# blink1_trinket0.net
KiCad netlist of a schematic drawn in EAGLE
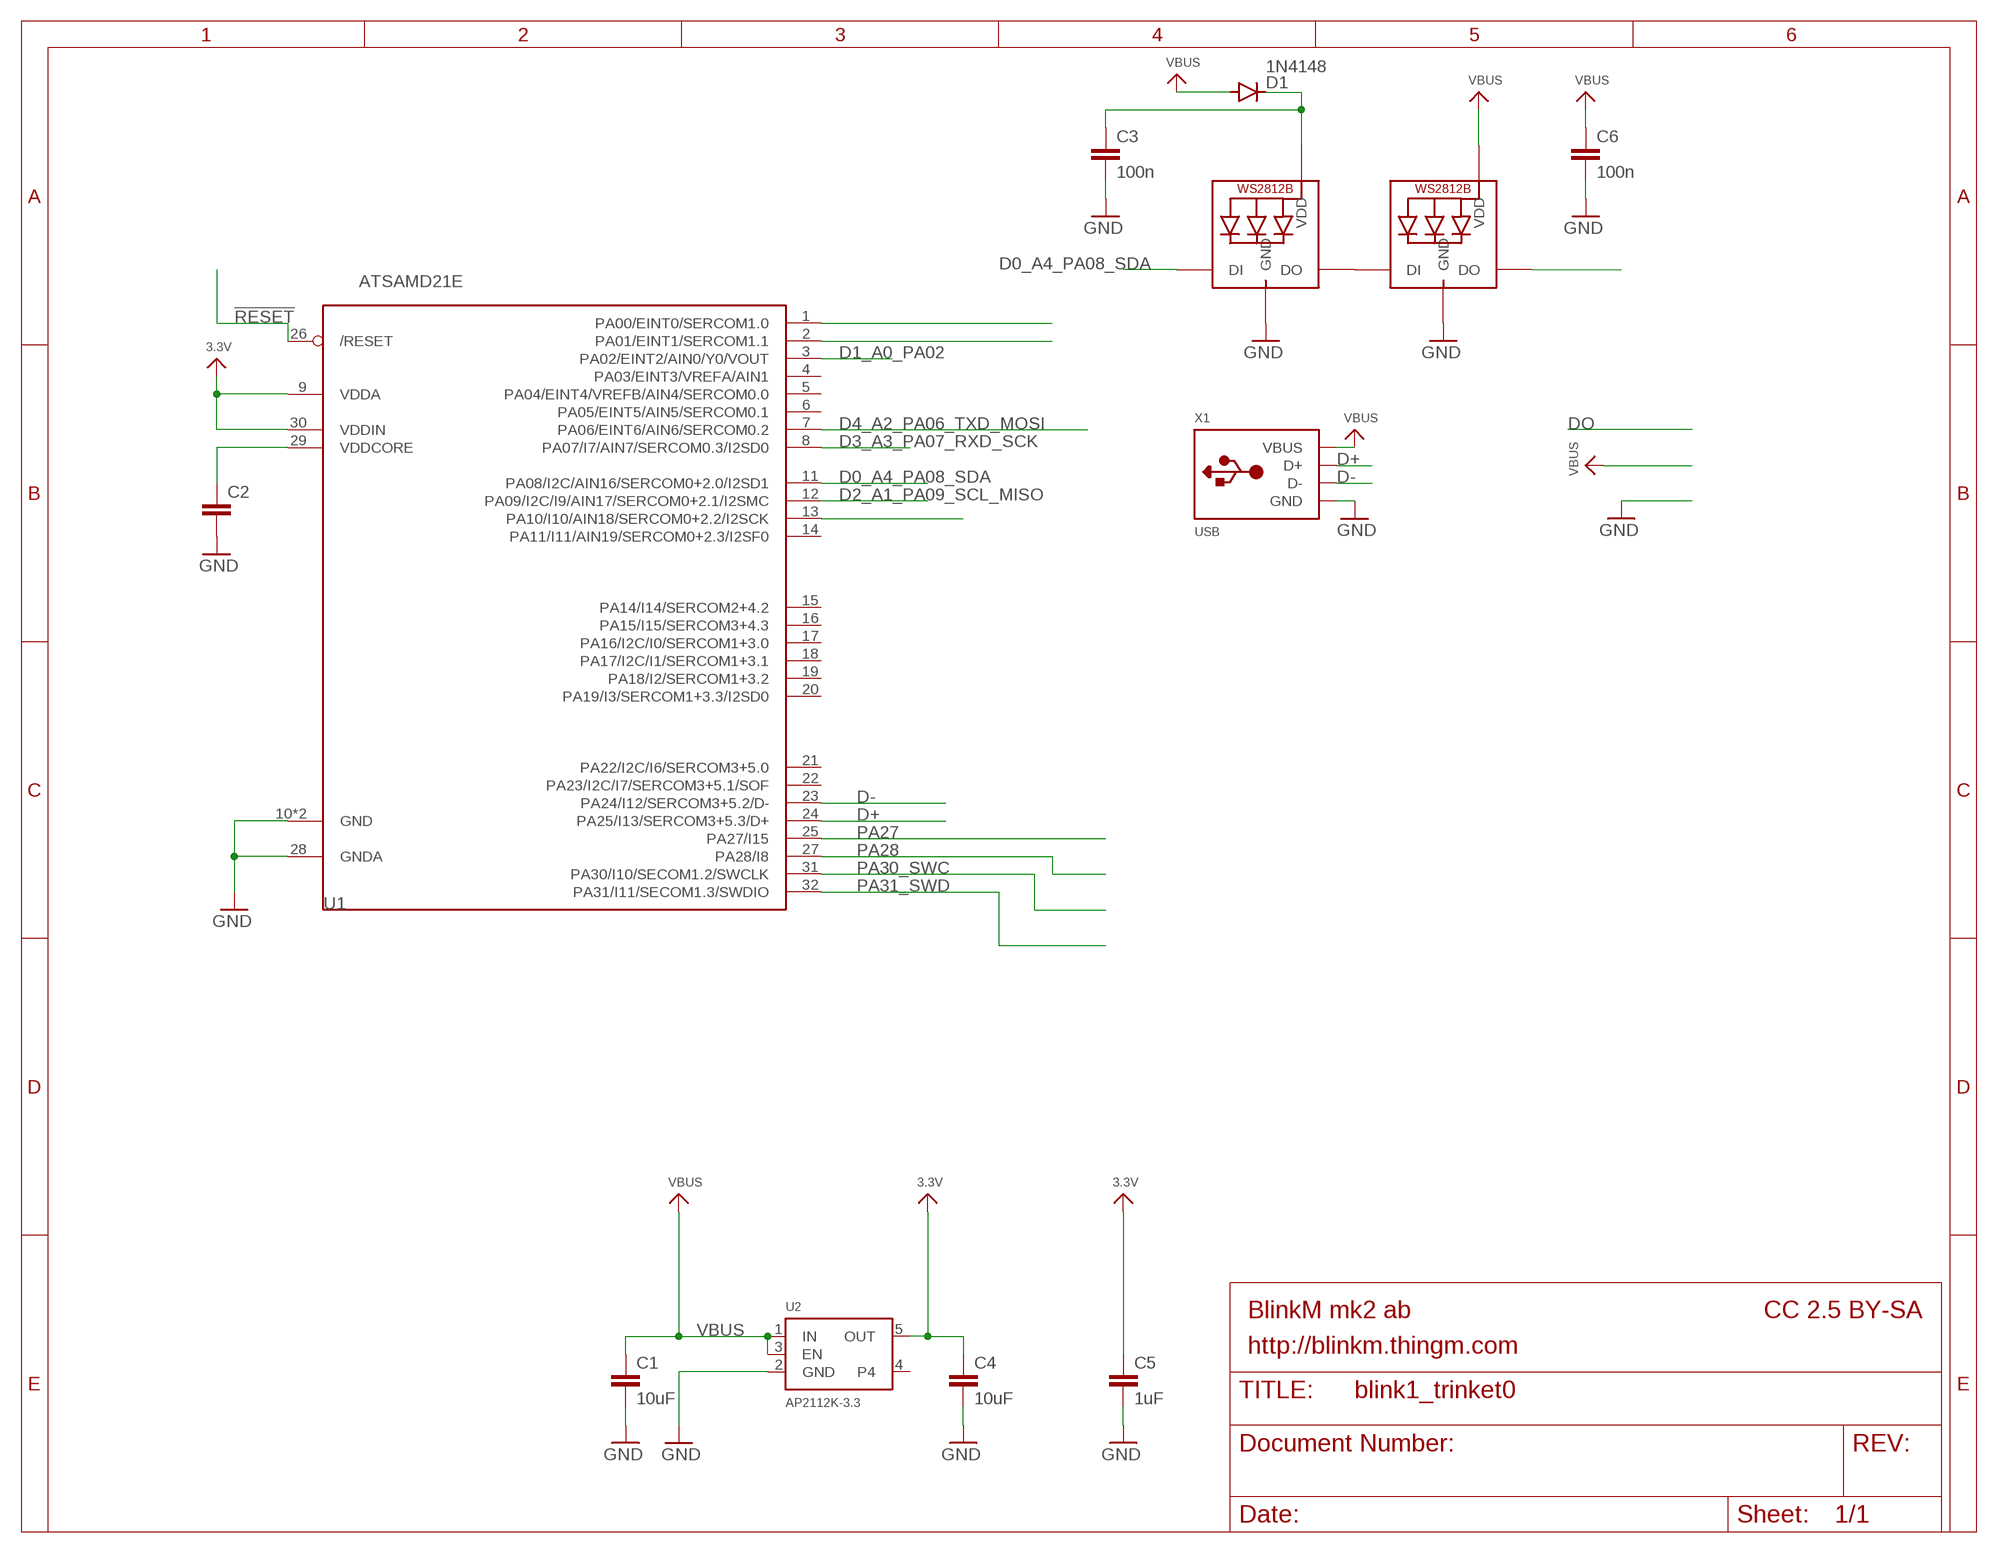
[diagram p0: schematic, sheet 1]

(export (version "E")
  (design (tool "Eeschema 10.0.6"))
  (components
    (comp (ref "C1")
      (value "10uF")
      (footprint "eagle-import:C0402")
      (libsource (lib "eagle-import") (part "C-EUC0402"))
    )
    (comp (ref "C2")
      (value "C-EUC0402")
      (footprint "eagle-import:C0402")
      (libsource (lib "eagle-import") (part "C-EUC0402"))
    )
    (comp (ref "C3")
      (value "100n")
      (footprint "eagle-import:C0402")
      (libsource (lib "eagle-import") (part "C-EUC0402"))
    )
    (comp (ref "C4")
      (value "10uF")
      (footprint "eagle-import:C0402")
      (libsource (lib "eagle-import") (part "C-EUC0402"))
    )
    (comp (ref "C5")
      (value "1uF")
      (footprint "eagle-import:C0402")
      (libsource (lib "eagle-import") (part "C-EUC0402"))
    )
    (comp (ref "C6")
      (value "100n")
      (footprint "eagle-import:C0402")
      (libsource (lib "eagle-import") (part "C-EUC0402"))
    )
    (comp (ref "D1")
      (value "1N4148")
      (footprint "eagle-import:SOD523")
      (libsource (lib "eagle-import") (part "DIODE-SOD523"))
    )
    (comp (ref "L1")
      (value "WS2812B3535")
      (footprint "eagle-import:LED3535")
      (libsource (lib "eagle-import") (part "WS2812B3535"))
    )
    (comp (ref "L2")
      (value "WS2812B3535")
      (footprint "eagle-import:LED3535")
      (libsource (lib "eagle-import") (part "WS2812B3535"))
    )
    (comp (ref "U1")
      (value "ATSAMD21E")
      (footprint "eagle-import:QFN32_5MM")
      (libsource (lib "eagle-import") (part "ATSAMD21E"))
    )
    (comp (ref "U2")
      (value "AP2112K-3.3")
      (footprint "eagle-import:SOT23-5")
      (libsource (lib "eagle-import") (part "VREG_SOT23-5"))
    )
    (comp (ref "X1")
      (value "USB")
      (footprint "eagle-import:MOLEX-48037-1000")
      (libsource (lib "eagle-import") (part "USB"))
    )
  )
  (nets
    (net (code "1") (name "/D+") (class "Default")
      (node (ref "U1") (pin "24") (pinfunction "PA25/I13/SERCOM3+5.3/D+_24") (pintype "bidirectional"))
      (node (ref "X1") (pin "3") (pinfunction "D+_3") (pintype "bidirectional"))
    )
    (net (code "2") (name "/D-") (class "Default")
      (node (ref "U1") (pin "23") (pinfunction "PA24/I12/SERCOM3+5.2/D-_23") (pintype "bidirectional"))
      (node (ref "X1") (pin "2") (pinfunction "D-_2") (pintype "bidirectional"))
    )
    (net (code "3") (name "/D0_A4_PA08_SDA") (class "Default")
      (node (ref "L1") (pin "1") (pinfunction "DI_1") (pintype "input"))
      (node (ref "U1") (pin "11") (pinfunction "PA08/I2C/AIN16/SERCOM0+2.0/I2SD1_11") (pintype "bidirectional"))
    )
    (net (code "4") (name "/D1_A0_PA02") (class "Default")
      (node (ref "U1") (pin "3") (pinfunction "PA02/EINT2/AIN0/Y0/VOUT_3") (pintype "bidirectional"))
    )
    (net (code "5") (name "/D2_A1_PA09_SCL_MISO") (class "Default")
      (node (ref "U1") (pin "12") (pinfunction "PA09/I2C/I9/AIN17/SERCOM0+2.1/I2SMC_12") (pintype "bidirectional"))
    )
    (net (code "6") (name "/D3_A3_PA07_RXD_SCK") (class "Default")
      (node (ref "U1") (pin "8") (pinfunction "PA07/I7/AIN7/SERCOM0.3/I2SD0_8") (pintype "bidirectional"))
    )
    (net (code "7") (name "/D4_A2_PA06_TXD_MOSI") (class "Default")
      (node (ref "U1") (pin "7") (pinfunction "PA06/EINT6/AIN6/SERCOM0.2_7") (pintype "bidirectional"))
    )
    (net (code "8") (name "/DO") (class "Default")
      (node (ref "L2") (pin "3") (pinfunction "DO_3") (pintype "output"))
    )
    (net (code "9") (name "/PA27") (class "Default")
      (node (ref "U1") (pin "25") (pinfunction "PA27/I15_25") (pintype "bidirectional"))
    )
    (net (code "10") (name "/PA28") (class "Default")
      (node (ref "U1") (pin "27") (pinfunction "PA28/I8_27") (pintype "bidirectional"))
    )
    (net (code "11") (name "/PA30_SWC") (class "Default")
      (node (ref "U1") (pin "31") (pinfunction "PA30/I10/SECOM1.2/SWCLK_31") (pintype "bidirectional"))
    )
    (net (code "12") (name "/PA31_SWD") (class "Default")
      (node (ref "U1") (pin "32") (pinfunction "PA31/I11/SECOM1.3/SWDIO_32") (pintype "bidirectional"))
    )
    (net (code "13") (name "/~{RESET}") (class "Default")
      (node (ref "U1") (pin "26") (pinfunction "/RESET_26") (pintype "bidirectional"))
    )
    (net (code "14") (name "3.3V") (class "Default")
      (node (ref "C4") (pin "1") (pinfunction "1_1") (pintype "passive"))
      (node (ref "C5") (pin "1") (pinfunction "1_1") (pintype "passive"))
      (node (ref "U1") (pin "30") (pinfunction "VDDIN_30") (pintype "power_in"))
      (node (ref "U1") (pin "9") (pinfunction "VDDA_9") (pintype "power_in"))
      (node (ref "U2") (pin "5") (pinfunction "OUT_5") (pintype "power_in"))
    )
    (net (code "15") (name "GND") (class "Default")
      (node (ref "C1") (pin "2") (pinfunction "2_2") (pintype "passive"))
      (node (ref "C2") (pin "2") (pinfunction "2_2") (pintype "passive"))
      (node (ref "C3") (pin "2") (pinfunction "2_2") (pintype "passive"))
      (node (ref "C4") (pin "2") (pinfunction "2_2") (pintype "passive"))
      (node (ref "C5") (pin "2") (pinfunction "2_2") (pintype "passive"))
      (node (ref "C6") (pin "2") (pinfunction "2_2") (pintype "passive"))
      (node (ref "L1") (pin "4") (pinfunction "GND_4") (pintype "power_in"))
      (node (ref "L2") (pin "4") (pinfunction "GND_4") (pintype "power_in"))
      (node (ref "U1") (pin "10") (pinfunction "GND_10") (pintype "power_in"))
      (node (ref "U1") (pin "28") (pinfunction "GNDA_28") (pintype "power_in"))
      (node (ref "U1") (pin "33") (pinfunction "GND_33") (pintype "power_in"))
      (node (ref "U2") (pin "2") (pinfunction "GND_2") (pintype "power_in"))
      (node (ref "X1") (pin "4") (pinfunction "GND_4") (pintype "power_in"))
    )
    (net (code "16") (name "Net-(L1-DO)") (class "Default")
      (node (ref "L1") (pin "3") (pinfunction "DO_3") (pintype "output"))
      (node (ref "L2") (pin "1") (pinfunction "DI_1") (pintype "input"))
    )
    (net (code "17") (name "Net-(L1-VDD)") (class "Default")
      (node (ref "C3") (pin "1") (pinfunction "1_1") (pintype "passive"))
      (node (ref "D1") (pin "C") (pinfunction "C_C") (pintype "passive"))
      (node (ref "L1") (pin "2") (pinfunction "VDD_2") (pintype "power_in"))
    )
    (net (code "18") (name "Net-(U1-VDDCORE)") (class "Default")
      (node (ref "C2") (pin "1") (pinfunction "1_1") (pintype "passive"))
      (node (ref "U1") (pin "29") (pinfunction "VDDCORE_29") (pintype "power_in"))
    )
    (net (code "19") (name "VBUS") (class "Default")
      (node (ref "C1") (pin "1") (pinfunction "1_1") (pintype "passive"))
      (node (ref "C6") (pin "1") (pinfunction "1_1") (pintype "passive"))
      (node (ref "D1") (pin "A") (pinfunction "A_A") (pintype "passive"))
      (node (ref "L2") (pin "2") (pinfunction "VDD_2") (pintype "power_in"))
      (node (ref "U2") (pin "1") (pinfunction "IN_1") (pintype "power_in"))
      (node (ref "U2") (pin "3") (pinfunction "EN_3") (pintype "input"))
      (node (ref "X1") (pin "1") (pinfunction "VBUS_1") (pintype "power_in"))
    )
    (net (code "20") (name "unconnected-(U1-PA00{slash}EINT0{slash}SERCOM1.0-Pad1)") (class "Default")
      (node (ref "U1") (pin "1") (pinfunction "PA00/EINT0/SERCOM1.0_1") (pintype "bidirectional"))
    )
    (net (code "21") (name "unconnected-(U1-PA01{slash}EINT1{slash}SERCOM1.1-Pad2)") (class "Default")
      (node (ref "U1") (pin "2") (pinfunction "PA01/EINT1/SERCOM1.1_2") (pintype "bidirectional"))
    )
    (net (code "22") (name "unconnected-(U1-PA03{slash}EINT3{slash}VREFA{slash}AIN1-Pad4)") (class "Default")
      (node (ref "U1") (pin "4") (pinfunction "PA03/EINT3/VREFA/AIN1_4") (pintype "bidirectional"))
    )
    (net (code "23") (name "unconnected-(U1-PA04{slash}EINT4{slash}VREFB{slash}AIN4{slash}SERCOM0.0-Pad5)") (class "Default")
      (node (ref "U1") (pin "5") (pinfunction "PA04/EINT4/VREFB/AIN4/SERCOM0.0_5") (pintype "bidirectional"))
    )
    (net (code "24") (name "unconnected-(U1-PA05{slash}EINT5{slash}AIN5{slash}SERCOM0.1-Pad6)") (class "Default")
      (node (ref "U1") (pin "6") (pinfunction "PA05/EINT5/AIN5/SERCOM0.1_6") (pintype "bidirectional"))
    )
    (net (code "25") (name "unconnected-(U1-PA10{slash}I10{slash}AIN18{slash}SERCOM0+2.2{slash}I2SCK-Pad13)") (class "Default")
      (node (ref "U1") (pin "13") (pinfunction "PA10/I10/AIN18/SERCOM0+2.2/I2SCK_13") (pintype "bidirectional"))
    )
    (net (code "26") (name "unconnected-(U1-PA11{slash}I11{slash}AIN19{slash}SERCOM0+2.3{slash}I2SF0-Pad14)") (class "Default")
      (node (ref "U1") (pin "14") (pinfunction "PA11/I11/AIN19/SERCOM0+2.3/I2SF0_14") (pintype "bidirectional"))
    )
    (net (code "27") (name "unconnected-(U1-PA14{slash}I14{slash}SERCOM2+4.2-Pad15)") (class "Default")
      (node (ref "U1") (pin "15") (pinfunction "PA14/I14/SERCOM2+4.2_15") (pintype "bidirectional"))
    )
    (net (code "28") (name "unconnected-(U1-PA15{slash}I15{slash}SERCOM3+4.3-Pad16)") (class "Default")
      (node (ref "U1") (pin "16") (pinfunction "PA15/I15/SERCOM3+4.3_16") (pintype "bidirectional"))
    )
    (net (code "29") (name "unconnected-(U1-PA16{slash}I2C{slash}I0{slash}SERCOM1+3.0-Pad17)") (class "Default")
      (node (ref "U1") (pin "17") (pinfunction "PA16/I2C/I0/SERCOM1+3.0_17") (pintype "bidirectional"))
    )
    (net (code "30") (name "unconnected-(U1-PA17{slash}I2C{slash}I1{slash}SERCOM1+3.1-Pad18)") (class "Default")
      (node (ref "U1") (pin "18") (pinfunction "PA17/I2C/I1/SERCOM1+3.1_18") (pintype "bidirectional"))
    )
    (net (code "31") (name "unconnected-(U1-PA18{slash}I2{slash}SERCOM1+3.2-Pad19)") (class "Default")
      (node (ref "U1") (pin "19") (pinfunction "PA18/I2/SERCOM1+3.2_19") (pintype "bidirectional"))
    )
    (net (code "32") (name "unconnected-(U1-PA19{slash}I3{slash}SERCOM1+3.3{slash}I2SD0-Pad20)") (class "Default")
      (node (ref "U1") (pin "20") (pinfunction "PA19/I3/SERCOM1+3.3/I2SD0_20") (pintype "bidirectional"))
    )
    (net (code "33") (name "unconnected-(U1-PA22{slash}I2C{slash}I6{slash}SERCOM3+5.0-Pad21)") (class "Default")
      (node (ref "U1") (pin "21") (pinfunction "PA22/I2C/I6/SERCOM3+5.0_21") (pintype "bidirectional"))
    )
    (net (code "34") (name "unconnected-(U1-PA23{slash}I2C{slash}I7{slash}SERCOM3+5.1{slash}SOF-Pad22)") (class "Default")
      (node (ref "U1") (pin "22") (pinfunction "PA23/I2C/I7/SERCOM3+5.1/SOF_22") (pintype "bidirectional"))
    )
    (net (code "35") (name "unconnected-(U2-P4-Pad4)") (class "Default")
      (node (ref "U2") (pin "4") (pinfunction "P4_4") (pintype "bidirectional"))
    )
  )
)
